# MCU.net
KiCad netlist of a schematic drawn in Altium Designer
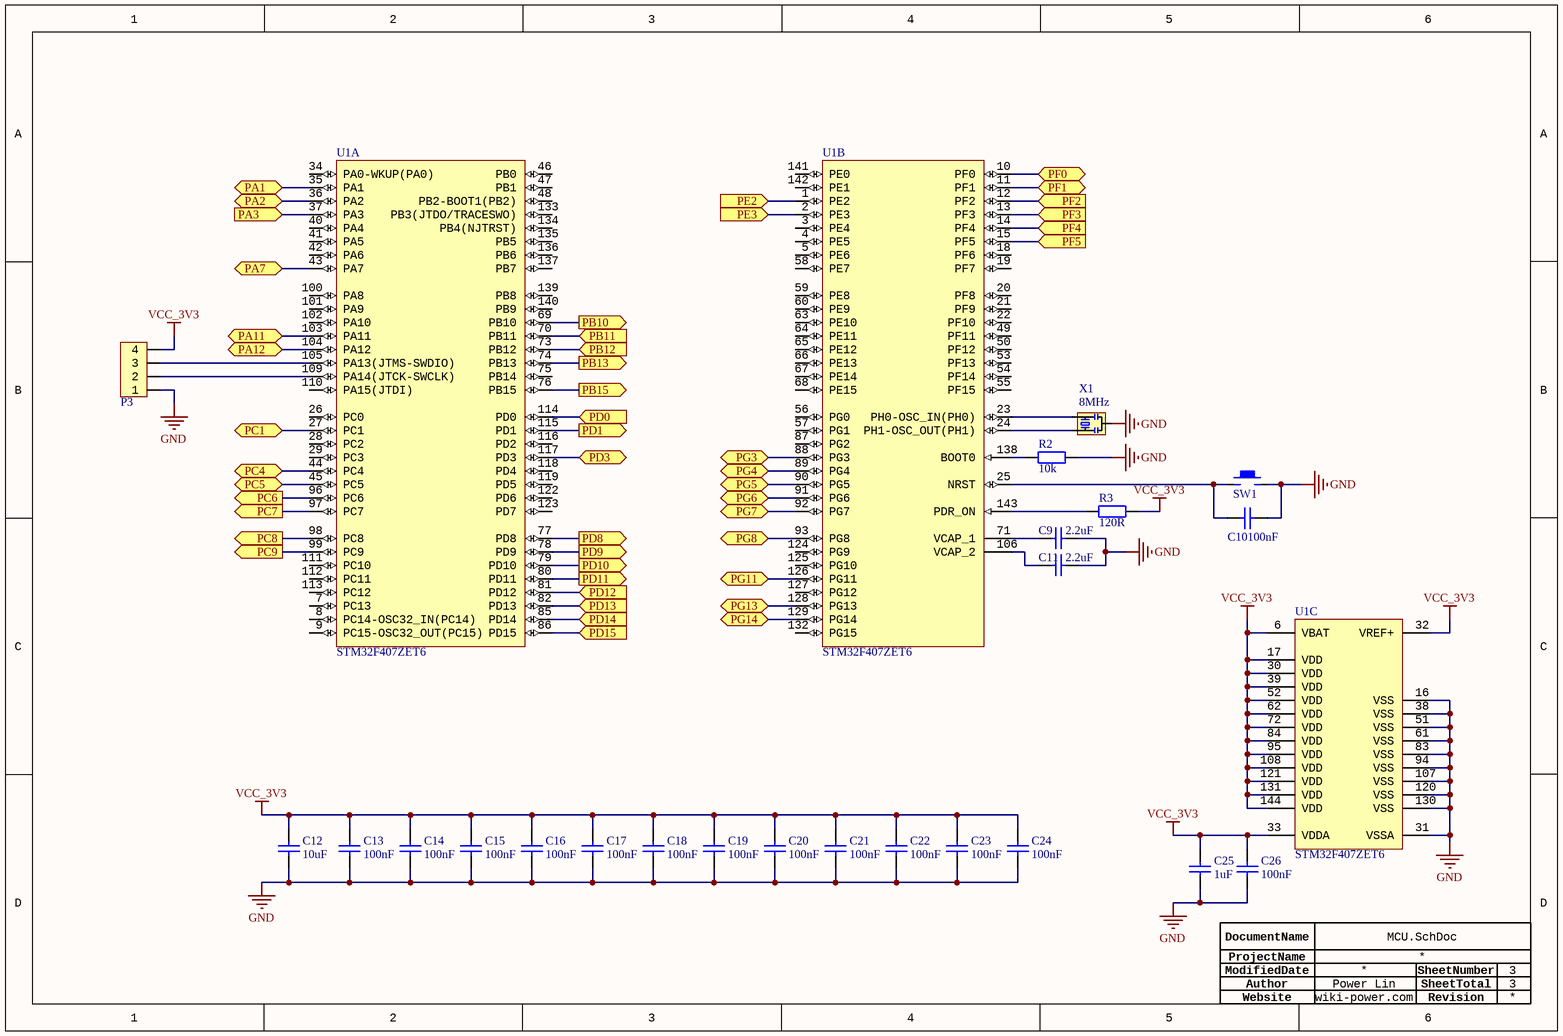
[diagram p0: MCU.SchDoc]

(export (version "E")
  (design (tool "Eeschema 10.0.6"))
  (components
    (comp (ref "C9")
      (value "2.2uF")
      (footprint "CAP-0603")
      (description "贴片电容")
      (libsource (lib "Power_Lib_Altium") (part "CAP"))
    )
    (comp (ref "C10")
      (value "100nF")
      (footprint "CAP-0603")
      (description "贴片电容")
      (libsource (lib "Power_Lib_Altium") (part "CAP"))
    )
    (comp (ref "C11")
      (value "2.2uF")
      (footprint "CAP-0603")
      (description "贴片电容")
      (libsource (lib "Power_Lib_Altium") (part "CAP"))
    )
    (comp (ref "C12")
      (value "10uF")
      (footprint "CAP-0603")
      (description "贴片电容")
      (libsource (lib "Power_Lib_Altium") (part "CAP"))
    )
    (comp (ref "C13")
      (value "100nF")
      (footprint "CAP-0603")
      (description "贴片电容")
      (libsource (lib "Power_Lib_Altium") (part "CAP"))
    )
    (comp (ref "C14")
      (value "100nF")
      (footprint "CAP-0603")
      (description "贴片电容")
      (libsource (lib "Power_Lib_Altium") (part "CAP"))
    )
    (comp (ref "C15")
      (value "100nF")
      (footprint "CAP-0603")
      (description "贴片电容")
      (libsource (lib "Power_Lib_Altium") (part "CAP"))
    )
    (comp (ref "C16")
      (value "100nF")
      (footprint "CAP-0603")
      (description "贴片电容")
      (libsource (lib "Power_Lib_Altium") (part "CAP"))
    )
    (comp (ref "C17")
      (value "100nF")
      (footprint "CAP-0603")
      (description "贴片电容")
      (libsource (lib "Power_Lib_Altium") (part "CAP"))
    )
    (comp (ref "C18")
      (value "100nF")
      (footprint "CAP-0603")
      (description "贴片电容")
      (libsource (lib "Power_Lib_Altium") (part "CAP"))
    )
    (comp (ref "C19")
      (value "100nF")
      (footprint "CAP-0603")
      (description "贴片电容")
      (libsource (lib "Power_Lib_Altium") (part "CAP"))
    )
    (comp (ref "C20")
      (value "100nF")
      (footprint "CAP-0603")
      (description "贴片电容")
      (libsource (lib "Power_Lib_Altium") (part "CAP"))
    )
    (comp (ref "C21")
      (value "100nF")
      (footprint "CAP-0603")
      (description "贴片电容")
      (libsource (lib "Power_Lib_Altium") (part "CAP"))
    )
    (comp (ref "C22")
      (value "100nF")
      (footprint "CAP-0603")
      (description "贴片电容")
      (libsource (lib "Power_Lib_Altium") (part "CAP"))
    )
    (comp (ref "C23")
      (value "100nF")
      (footprint "CAP-0603")
      (description "贴片电容")
      (libsource (lib "Power_Lib_Altium") (part "CAP"))
    )
    (comp (ref "C24")
      (value "100nF")
      (footprint "CAP-0603")
      (description "贴片电容")
      (libsource (lib "Power_Lib_Altium") (part "CAP"))
    )
    (comp (ref "C25")
      (value "1uF")
      (footprint "CAP-0603")
      (description "贴片电容")
      (libsource (lib "Power_Lib_Altium") (part "CAP"))
    )
    (comp (ref "C26")
      (value "100nF")
      (footprint "CAP-0603")
      (description "贴片电容")
      (libsource (lib "Power_Lib_Altium") (part "CAP"))
    )
    (comp (ref "P3")
      (value "HDR1x4_2.54")
      (footprint "HDR1x4_2.54_180")
      (description "Header")
      (libsource (lib "Power_Lib_Altium") (part "HDR1x4_2.54"))
    )
    (comp (ref "R2")
      (value "10k")
      (footprint "R-0603")
      (description "贴片电阻")
      (libsource (lib "Power_Lib_Altium") (part "RES"))
    )
    (comp (ref "R3")
      (value "120R")
      (footprint "R-0603")
      (description "贴片电阻")
      (libsource (lib "Power_Lib_Altium") (part "RES"))
    )
    (comp (ref "SW1")
      (value "KEY")
      (footprint "KEY-4P-4.2*3.4*2.5")
      (description "按键开关")
      (libsource (lib "Power_Lib_Altium") (part "KEY"))
    )
    (comp (ref "U1")
      (value "STM32F407ZET6")
      (footprint "STM-LQFP144_N")
      (fields (field (name "MANUFACTURER") "STMicroelectronics"))
      (libsource (lib "Power_Lib_Altium") (part "STM32F407ZET6"))
    )
    (comp (ref "X1")
      (value "8MHz")
      (footprint "SMD3213-3P")
      (description "CSTCE8M00G15C99-R0")
      (libsource (lib "Power_Lib_Altium") (part "XTAL"))
    )
  )
  (nets
    (net (code "1") (name "/PA1") (class "Default")
      (node (ref "U1") (pin "35") (pinfunction "PA1_35") (pintype "bidirectional"))
    )
    (net (code "2") (name "/PA2") (class "Default")
      (node (ref "U1") (pin "36") (pinfunction "PA2_36") (pintype "bidirectional"))
    )
    (net (code "3") (name "/PA3") (class "Default")
      (node (ref "U1") (pin "37") (pinfunction "PA3_37") (pintype "bidirectional"))
    )
    (net (code "4") (name "/PA7") (class "Default")
      (node (ref "U1") (pin "43") (pinfunction "PA7_43") (pintype "bidirectional"))
    )
    (net (code "5") (name "/PA11") (class "Default")
      (node (ref "U1") (pin "103") (pinfunction "PA11_103") (pintype "bidirectional"))
    )
    (net (code "6") (name "/PA12") (class "Default")
      (node (ref "U1") (pin "104") (pinfunction "PA12_104") (pintype "bidirectional"))
    )
    (net (code "7") (name "/PB10") (class "Default")
      (node (ref "U1") (pin "69") (pinfunction "PB10_69") (pintype "bidirectional"))
    )
    (net (code "8") (name "/PB11") (class "Default")
      (node (ref "U1") (pin "70") (pinfunction "PB11_70") (pintype "bidirectional"))
    )
    (net (code "9") (name "/PB12") (class "Default")
      (node (ref "U1") (pin "73") (pinfunction "PB12_73") (pintype "bidirectional"))
    )
    (net (code "10") (name "/PB13") (class "Default")
      (node (ref "U1") (pin "74") (pinfunction "PB13_74") (pintype "bidirectional"))
    )
    (net (code "11") (name "/PB15") (class "Default")
      (node (ref "U1") (pin "76") (pinfunction "PB15_76") (pintype "bidirectional"))
    )
    (net (code "12") (name "/PC1") (class "Default")
      (node (ref "U1") (pin "27") (pinfunction "PC1_27") (pintype "bidirectional"))
    )
    (net (code "13") (name "/PC4") (class "Default")
      (node (ref "U1") (pin "44") (pinfunction "PC4_44") (pintype "bidirectional"))
    )
    (net (code "14") (name "/PC5") (class "Default")
      (node (ref "U1") (pin "45") (pinfunction "PC5_45") (pintype "bidirectional"))
    )
    (net (code "15") (name "/PC6") (class "Default")
      (node (ref "U1") (pin "96") (pinfunction "PC6_96") (pintype "bidirectional"))
    )
    (net (code "16") (name "/PC7") (class "Default")
      (node (ref "U1") (pin "97") (pinfunction "PC7_97") (pintype "bidirectional"))
    )
    (net (code "17") (name "/PC8") (class "Default")
      (node (ref "U1") (pin "98") (pinfunction "PC8_98") (pintype "bidirectional"))
    )
    (net (code "18") (name "/PC9") (class "Default")
      (node (ref "U1") (pin "99") (pinfunction "PC9_99") (pintype "bidirectional"))
    )
    (net (code "19") (name "/PD0") (class "Default")
      (node (ref "U1") (pin "114") (pinfunction "PD0_114") (pintype "bidirectional"))
    )
    (net (code "20") (name "/PD1") (class "Default")
      (node (ref "U1") (pin "115") (pinfunction "PD1_115") (pintype "bidirectional"))
    )
    (net (code "21") (name "/PD3") (class "Default")
      (node (ref "U1") (pin "117") (pinfunction "PD3_117") (pintype "bidirectional"))
    )
    (net (code "22") (name "/PD8") (class "Default")
      (node (ref "U1") (pin "77") (pinfunction "PD8_77") (pintype "bidirectional"))
    )
    (net (code "23") (name "/PD9") (class "Default")
      (node (ref "U1") (pin "78") (pinfunction "PD9_78") (pintype "bidirectional"))
    )
    (net (code "24") (name "/PD10") (class "Default")
      (node (ref "U1") (pin "79") (pinfunction "PD10_79") (pintype "bidirectional"))
    )
    (net (code "25") (name "/PD11") (class "Default")
      (node (ref "U1") (pin "80") (pinfunction "PD11_80") (pintype "bidirectional"))
    )
    (net (code "26") (name "/PD12") (class "Default")
      (node (ref "U1") (pin "81") (pinfunction "PD12_81") (pintype "bidirectional"))
    )
    (net (code "27") (name "/PD13") (class "Default")
      (node (ref "U1") (pin "82") (pinfunction "PD13_82") (pintype "bidirectional"))
    )
    (net (code "28") (name "/PD14") (class "Default")
      (node (ref "U1") (pin "85") (pinfunction "PD14_85") (pintype "bidirectional"))
    )
    (net (code "29") (name "/PD15") (class "Default")
      (node (ref "U1") (pin "86") (pinfunction "PD15_86") (pintype "bidirectional"))
    )
    (net (code "30") (name "/PE2") (class "Default")
      (node (ref "U1") (pin "1") (pinfunction "PE2_1") (pintype "bidirectional"))
    )
    (net (code "31") (name "/PE3") (class "Default")
      (node (ref "U1") (pin "2") (pinfunction "PE3_2") (pintype "bidirectional"))
    )
    (net (code "32") (name "/PF0") (class "Default")
      (node (ref "U1") (pin "10") (pinfunction "PF0_10") (pintype "bidirectional"))
    )
    (net (code "33") (name "/PF1") (class "Default")
      (node (ref "U1") (pin "11") (pinfunction "PF1_11") (pintype "bidirectional"))
    )
    (net (code "34") (name "/PF2") (class "Default")
      (node (ref "U1") (pin "12") (pinfunction "PF2_12") (pintype "bidirectional"))
    )
    (net (code "35") (name "/PF3") (class "Default")
      (node (ref "U1") (pin "13") (pinfunction "PF3_13") (pintype "bidirectional"))
    )
    (net (code "36") (name "/PF4") (class "Default")
      (node (ref "U1") (pin "14") (pinfunction "PF4_14") (pintype "bidirectional"))
    )
    (net (code "37") (name "/PF5") (class "Default")
      (node (ref "U1") (pin "15") (pinfunction "PF5_15") (pintype "bidirectional"))
    )
    (net (code "38") (name "/PG3") (class "Default")
      (node (ref "U1") (pin "88") (pinfunction "PG3_88") (pintype "bidirectional"))
    )
    (net (code "39") (name "/PG4") (class "Default")
      (node (ref "U1") (pin "89") (pinfunction "PG4_89") (pintype "bidirectional"))
    )
    (net (code "40") (name "/PG5") (class "Default")
      (node (ref "U1") (pin "90") (pinfunction "PG5_90") (pintype "bidirectional"))
    )
    (net (code "41") (name "/PG6") (class "Default")
      (node (ref "U1") (pin "91") (pinfunction "PG6_91") (pintype "bidirectional"))
    )
    (net (code "42") (name "/PG7") (class "Default")
      (node (ref "U1") (pin "92") (pinfunction "PG7_92") (pintype "bidirectional"))
    )
    (net (code "43") (name "/PG8") (class "Default")
      (node (ref "U1") (pin "93") (pinfunction "PG8_93") (pintype "bidirectional"))
    )
    (net (code "44") (name "/PG11") (class "Default")
      (node (ref "U1") (pin "126") (pinfunction "PG11_126") (pintype "bidirectional"))
    )
    (net (code "45") (name "/PG13") (class "Default")
      (node (ref "U1") (pin "128") (pinfunction "PG13_128") (pintype "bidirectional"))
    )
    (net (code "46") (name "/PG14") (class "Default")
      (node (ref "U1") (pin "129") (pinfunction "PG14_129") (pintype "bidirectional"))
    )
    (net (code "47") (name "GND") (class "Default")
      (node (ref "C10") (pin "1") (pinfunction "1_1") (pintype "passive"))
      (node (ref "C11") (pin "2") (pinfunction "2_2") (pintype "passive"))
      (node (ref "C12") (pin "1") (pinfunction "1_1") (pintype "passive"))
      (node (ref "C13") (pin "1") (pinfunction "1_1") (pintype "passive"))
      (node (ref "C14") (pin "1") (pinfunction "1_1") (pintype "passive"))
      (node (ref "C15") (pin "1") (pinfunction "1_1") (pintype "passive"))
      (node (ref "C16") (pin "1") (pinfunction "1_1") (pintype "passive"))
      (node (ref "C17") (pin "1") (pinfunction "1_1") (pintype "passive"))
      (node (ref "C18") (pin "1") (pinfunction "1_1") (pintype "passive"))
      (node (ref "C19") (pin "1") (pinfunction "1_1") (pintype "passive"))
      (node (ref "C20") (pin "1") (pinfunction "1_1") (pintype "passive"))
      (node (ref "C21") (pin "1") (pinfunction "1_1") (pintype "passive"))
      (node (ref "C22") (pin "1") (pinfunction "1_1") (pintype "passive"))
      (node (ref "C23") (pin "1") (pinfunction "1_1") (pintype "passive"))
      (node (ref "C24") (pin "1") (pinfunction "1_1") (pintype "passive"))
      (node (ref "C25") (pin "1") (pinfunction "1_1") (pintype "passive"))
      (node (ref "C26") (pin "1") (pinfunction "1_1") (pintype "passive"))
      (node (ref "C9") (pin "2") (pinfunction "2_2") (pintype "passive"))
      (node (ref "P3") (pin "1") (pinfunction "1_1") (pintype "passive"))
      (node (ref "R2") (pin "1") (pinfunction "1_1") (pintype "passive"))
      (node (ref "SW1") (pin "2") (pinfunction "2_2") (pintype "passive"))
      (node (ref "U1") (pin "107") (pinfunction "VSS_107") (pintype "power_in"))
      (node (ref "U1") (pin "120") (pinfunction "VSS_120") (pintype "power_in"))
      (node (ref "U1") (pin "130") (pinfunction "VSS_130") (pintype "power_in"))
      (node (ref "U1") (pin "16") (pinfunction "VSS_16") (pintype "power_in"))
      (node (ref "U1") (pin "31") (pinfunction "VSSA_31") (pintype "power_in"))
      (node (ref "U1") (pin "38") (pinfunction "VSS_38") (pintype "power_in"))
      (node (ref "U1") (pin "51") (pinfunction "VSS_51") (pintype "power_in"))
      (node (ref "U1") (pin "61") (pinfunction "VSS_61") (pintype "power_in"))
      (node (ref "U1") (pin "83") (pinfunction "VSS_83") (pintype "power_in"))
      (node (ref "U1") (pin "94") (pinfunction "VSS_94") (pintype "power_in"))
      (node (ref "X1") (pin "2") (pinfunction "GND_2") (pintype "passive"))
    )
    (net (code "48") (name "Net-(U1A-PA13(JTMS-SWDIO))") (class "Default")
      (node (ref "P3") (pin "3") (pinfunction "3_3") (pintype "passive"))
      (node (ref "U1") (pin "105") (pinfunction "PA13(JTMS-SWDIO)_105") (pintype "bidirectional"))
    )
    (net (code "49") (name "Net-(U1A-PA14(JTCK-SWCLK))") (class "Default")
      (node (ref "P3") (pin "2") (pinfunction "2_2") (pintype "passive"))
      (node (ref "U1") (pin "109") (pinfunction "PA14(JTCK-SWCLK)_109") (pintype "bidirectional"))
    )
    (net (code "50") (name "Net-(U1B-BOOT0)") (class "Default")
      (node (ref "R2") (pin "2") (pinfunction "2_2") (pintype "passive"))
      (node (ref "U1") (pin "138") (pinfunction "BOOT0_138") (pintype "input"))
    )
    (net (code "51") (name "Net-(U1B-NRST)") (class "Default")
      (node (ref "C10") (pin "2") (pinfunction "2_2") (pintype "passive"))
      (node (ref "SW1") (pin "1") (pinfunction "1_1") (pintype "passive"))
      (node (ref "U1") (pin "25") (pinfunction "NRST_25") (pintype "bidirectional"))
    )
    (net (code "52") (name "Net-(U1B-PDR_ON)") (class "Default")
      (node (ref "R3") (pin "2") (pinfunction "2_2") (pintype "passive"))
      (node (ref "U1") (pin "143") (pinfunction "PDR_ON_143") (pintype "input"))
    )
    (net (code "53") (name "Net-(U1B-PH0-OSC_IN(PH0))") (class "Default")
      (node (ref "U1") (pin "23") (pinfunction "PH0-OSC_IN(PH0)_23") (pintype "bidirectional"))
      (node (ref "X1") (pin "3") (pinfunction "OSC2_3") (pintype "passive"))
    )
    (net (code "54") (name "Net-(U1B-PH1-OSC_OUT(PH1))") (class "Default")
      (node (ref "U1") (pin "24") (pinfunction "PH1-OSC_OUT(PH1)_24") (pintype "bidirectional"))
      (node (ref "X1") (pin "1") (pinfunction "OSC1_1") (pintype "passive"))
    )
    (net (code "55") (name "Net-(U1B-VCAP_1)") (class "Default")
      (node (ref "C9") (pin "1") (pinfunction "1_1") (pintype "passive"))
      (node (ref "U1") (pin "71") (pinfunction "VCAP_1_71") (pintype "power_in"))
    )
    (net (code "56") (name "Net-(U1B-VCAP_2)") (class "Default")
      (node (ref "C11") (pin "1") (pinfunction "1_1") (pintype "passive"))
      (node (ref "U1") (pin "106") (pinfunction "VCAP_2_106") (pintype "power_in"))
    )
    (net (code "57") (name "VCC_3V3") (class "Default")
      (node (ref "C12") (pin "2") (pinfunction "2_2") (pintype "passive"))
      (node (ref "C13") (pin "2") (pinfunction "2_2") (pintype "passive"))
      (node (ref "C14") (pin "2") (pinfunction "2_2") (pintype "passive"))
      (node (ref "C15") (pin "2") (pinfunction "2_2") (pintype "passive"))
      (node (ref "C16") (pin "2") (pinfunction "2_2") (pintype "passive"))
      (node (ref "C17") (pin "2") (pinfunction "2_2") (pintype "passive"))
      (node (ref "C18") (pin "2") (pinfunction "2_2") (pintype "passive"))
      (node (ref "C19") (pin "2") (pinfunction "2_2") (pintype "passive"))
      (node (ref "C20") (pin "2") (pinfunction "2_2") (pintype "passive"))
      (node (ref "C21") (pin "2") (pinfunction "2_2") (pintype "passive"))
      (node (ref "C22") (pin "2") (pinfunction "2_2") (pintype "passive"))
      (node (ref "C23") (pin "2") (pinfunction "2_2") (pintype "passive"))
      (node (ref "C24") (pin "2") (pinfunction "2_2") (pintype "passive"))
      (node (ref "C25") (pin "2") (pinfunction "2_2") (pintype "passive"))
      (node (ref "C26") (pin "2") (pinfunction "2_2") (pintype "passive"))
      (node (ref "P3") (pin "4") (pinfunction "4_4") (pintype "passive"))
      (node (ref "R3") (pin "1") (pinfunction "1_1") (pintype "passive"))
      (node (ref "U1") (pin "108") (pinfunction "VDD_108") (pintype "power_in"))
      (node (ref "U1") (pin "121") (pinfunction "VDD_121") (pintype "power_in"))
      (node (ref "U1") (pin "131") (pinfunction "VDD_131") (pintype "power_in"))
      (node (ref "U1") (pin "144") (pinfunction "VDD_144") (pintype "power_in"))
      (node (ref "U1") (pin "17") (pinfunction "VDD_17") (pintype "power_in"))
      (node (ref "U1") (pin "30") (pinfunction "VDD_30") (pintype "power_in"))
      (node (ref "U1") (pin "32") (pinfunction "VREF+_32") (pintype "power_in"))
      (node (ref "U1") (pin "33") (pinfunction "VDDA_33") (pintype "power_in"))
      (node (ref "U1") (pin "39") (pinfunction "VDD_39") (pintype "power_in"))
      (node (ref "U1") (pin "52") (pinfunction "VDD_52") (pintype "power_in"))
      (node (ref "U1") (pin "6") (pinfunction "VBAT_6") (pintype "power_in"))
      (node (ref "U1") (pin "62") (pinfunction "VDD_62") (pintype "power_in"))
      (node (ref "U1") (pin "72") (pinfunction "VDD_72") (pintype "power_in"))
      (node (ref "U1") (pin "84") (pinfunction "VDD_84") (pintype "power_in"))
      (node (ref "U1") (pin "95") (pinfunction "VDD_95") (pintype "power_in"))
    )
    (net (code "58") (name "unconnected-(U1A-PA0-WKUP(PA0)-Pad34)") (class "Default")
      (node (ref "U1") (pin "34") (pinfunction "PA0-WKUP(PA0)_34") (pintype "bidirectional"))
    )
    (net (code "59") (name "unconnected-(U1A-PA4-Pad40)") (class "Default")
      (node (ref "U1") (pin "40") (pinfunction "PA4_40") (pintype "bidirectional"))
    )
    (net (code "60") (name "unconnected-(U1A-PA5-Pad41)") (class "Default")
      (node (ref "U1") (pin "41") (pinfunction "PA5_41") (pintype "bidirectional"))
    )
    (net (code "61") (name "unconnected-(U1A-PA6-Pad42)") (class "Default")
      (node (ref "U1") (pin "42") (pinfunction "PA6_42") (pintype "bidirectional"))
    )
    (net (code "62") (name "unconnected-(U1A-PA8-Pad100)") (class "Default")
      (node (ref "U1") (pin "100") (pinfunction "PA8_100") (pintype "bidirectional"))
    )
    (net (code "63") (name "unconnected-(U1A-PA9-Pad101)") (class "Default")
      (node (ref "U1") (pin "101") (pinfunction "PA9_101") (pintype "bidirectional"))
    )
    (net (code "64") (name "unconnected-(U1A-PA10-Pad102)") (class "Default")
      (node (ref "U1") (pin "102") (pinfunction "PA10_102") (pintype "bidirectional"))
    )
    (net (code "65") (name "unconnected-(U1A-PA15(JTDI)-Pad110)") (class "Default")
      (node (ref "U1") (pin "110") (pinfunction "PA15(JTDI)_110") (pintype "bidirectional"))
    )
    (net (code "66") (name "unconnected-(U1A-PB0-Pad46)") (class "Default")
      (node (ref "U1") (pin "46") (pinfunction "PB0_46") (pintype "bidirectional"))
    )
    (net (code "67") (name "unconnected-(U1A-PB1-Pad47)") (class "Default")
      (node (ref "U1") (pin "47") (pinfunction "PB1_47") (pintype "bidirectional"))
    )
    (net (code "68") (name "unconnected-(U1A-PB2-BOOT1(PB2)-Pad48)") (class "Default")
      (node (ref "U1") (pin "48") (pinfunction "PB2-BOOT1(PB2)_48") (pintype "bidirectional"))
    )
    (net (code "69") (name "unconnected-(U1A-PB3(JTDO{slash}TRACESWO)-Pad133)") (class "Default")
      (node (ref "U1") (pin "133") (pinfunction "PB3(JTDO/TRACESWO)_133") (pintype "bidirectional"))
    )
    (net (code "70") (name "unconnected-(U1A-PB4(NJTRST)-Pad134)") (class "Default")
      (node (ref "U1") (pin "134") (pinfunction "PB4(NJTRST)_134") (pintype "bidirectional"))
    )
    (net (code "71") (name "unconnected-(U1A-PB5-Pad135)") (class "Default")
      (node (ref "U1") (pin "135") (pinfunction "PB5_135") (pintype "bidirectional"))
    )
    (net (code "72") (name "unconnected-(U1A-PB6-Pad136)") (class "Default")
      (node (ref "U1") (pin "136") (pinfunction "PB6_136") (pintype "bidirectional"))
    )
    (net (code "73") (name "unconnected-(U1A-PB7-Pad137)") (class "Default")
      (node (ref "U1") (pin "137") (pinfunction "PB7_137") (pintype "bidirectional"))
    )
    (net (code "74") (name "unconnected-(U1A-PB8-Pad139)") (class "Default")
      (node (ref "U1") (pin "139") (pinfunction "PB8_139") (pintype "bidirectional"))
    )
    (net (code "75") (name "unconnected-(U1A-PB9-Pad140)") (class "Default")
      (node (ref "U1") (pin "140") (pinfunction "PB9_140") (pintype "bidirectional"))
    )
    (net (code "76") (name "unconnected-(U1A-PB14-Pad75)") (class "Default")
      (node (ref "U1") (pin "75") (pinfunction "PB14_75") (pintype "bidirectional"))
    )
    (net (code "77") (name "unconnected-(U1A-PC0-Pad26)") (class "Default")
      (node (ref "U1") (pin "26") (pinfunction "PC0_26") (pintype "bidirectional"))
    )
    (net (code "78") (name "unconnected-(U1A-PC2-Pad28)") (class "Default")
      (node (ref "U1") (pin "28") (pinfunction "PC2_28") (pintype "bidirectional"))
    )
    (net (code "79") (name "unconnected-(U1A-PC3-Pad29)") (class "Default")
      (node (ref "U1") (pin "29") (pinfunction "PC3_29") (pintype "bidirectional"))
    )
    (net (code "80") (name "unconnected-(U1A-PC10-Pad111)") (class "Default")
      (node (ref "U1") (pin "111") (pinfunction "PC10_111") (pintype "bidirectional"))
    )
    (net (code "81") (name "unconnected-(U1A-PC11-Pad112)") (class "Default")
      (node (ref "U1") (pin "112") (pinfunction "PC11_112") (pintype "bidirectional"))
    )
    (net (code "82") (name "unconnected-(U1A-PC12-Pad113)") (class "Default")
      (node (ref "U1") (pin "113") (pinfunction "PC12_113") (pintype "bidirectional"))
    )
    (net (code "83") (name "unconnected-(U1A-PC13-Pad7)") (class "Default")
      (node (ref "U1") (pin "7") (pinfunction "PC13_7") (pintype "bidirectional"))
    )
    (net (code "84") (name "unconnected-(U1A-PC14-OSC32_IN(PC14)-Pad8)") (class "Default")
      (node (ref "U1") (pin "8") (pinfunction "PC14-OSC32_IN(PC14)_8") (pintype "bidirectional"))
    )
    (net (code "85") (name "unconnected-(U1A-PC15-OSC32_OUT(PC15)-Pad9)") (class "Default")
      (node (ref "U1") (pin "9") (pinfunction "PC15-OSC32_OUT(PC15)_9") (pintype "bidirectional"))
    )
    (net (code "86") (name "unconnected-(U1A-PD2-Pad116)") (class "Default")
      (node (ref "U1") (pin "116") (pinfunction "PD2_116") (pintype "bidirectional"))
    )
    (net (code "87") (name "unconnected-(U1A-PD4-Pad118)") (class "Default")
      (node (ref "U1") (pin "118") (pinfunction "PD4_118") (pintype "bidirectional"))
    )
    (net (code "88") (name "unconnected-(U1A-PD5-Pad119)") (class "Default")
      (node (ref "U1") (pin "119") (pinfunction "PD5_119") (pintype "bidirectional"))
    )
    (net (code "89") (name "unconnected-(U1A-PD6-Pad122)") (class "Default")
      (node (ref "U1") (pin "122") (pinfunction "PD6_122") (pintype "bidirectional"))
    )
    (net (code "90") (name "unconnected-(U1A-PD7-Pad123)") (class "Default")
      (node (ref "U1") (pin "123") (pinfunction "PD7_123") (pintype "bidirectional"))
    )
    (net (code "91") (name "unconnected-(U1B-PE0-Pad141)") (class "Default")
      (node (ref "U1") (pin "141") (pinfunction "PE0_141") (pintype "bidirectional"))
    )
    (net (code "92") (name "unconnected-(U1B-PE1-Pad142)") (class "Default")
      (node (ref "U1") (pin "142") (pinfunction "PE1_142") (pintype "bidirectional"))
    )
    (net (code "93") (name "unconnected-(U1B-PE4-Pad3)") (class "Default")
      (node (ref "U1") (pin "3") (pinfunction "PE4_3") (pintype "bidirectional"))
    )
    (net (code "94") (name "unconnected-(U1B-PE5-Pad4)") (class "Default")
      (node (ref "U1") (pin "4") (pinfunction "PE5_4") (pintype "bidirectional"))
    )
    (net (code "95") (name "unconnected-(U1B-PE6-Pad5)") (class "Default")
      (node (ref "U1") (pin "5") (pinfunction "PE6_5") (pintype "bidirectional"))
    )
    (net (code "96") (name "unconnected-(U1B-PE7-Pad58)") (class "Default")
      (node (ref "U1") (pin "58") (pinfunction "PE7_58") (pintype "bidirectional"))
    )
    (net (code "97") (name "unconnected-(U1B-PE8-Pad59)") (class "Default")
      (node (ref "U1") (pin "59") (pinfunction "PE8_59") (pintype "bidirectional"))
    )
    (net (code "98") (name "unconnected-(U1B-PE9-Pad60)") (class "Default")
      (node (ref "U1") (pin "60") (pinfunction "PE9_60") (pintype "bidirectional"))
    )
    (net (code "99") (name "unconnected-(U1B-PE10-Pad63)") (class "Default")
      (node (ref "U1") (pin "63") (pinfunction "PE10_63") (pintype "bidirectional"))
    )
    (net (code "100") (name "unconnected-(U1B-PE11-Pad64)") (class "Default")
      (node (ref "U1") (pin "64") (pinfunction "PE11_64") (pintype "bidirectional"))
    )
    (net (code "101") (name "unconnected-(U1B-PE12-Pad65)") (class "Default")
      (node (ref "U1") (pin "65") (pinfunction "PE12_65") (pintype "bidirectional"))
    )
    (net (code "102") (name "unconnected-(U1B-PE13-Pad66)") (class "Default")
      (node (ref "U1") (pin "66") (pinfunction "PE13_66") (pintype "bidirectional"))
    )
    (net (code "103") (name "unconnected-(U1B-PE14-Pad67)") (class "Default")
      (node (ref "U1") (pin "67") (pinfunction "PE14_67") (pintype "bidirectional"))
    )
    (net (code "104") (name "unconnected-(U1B-PE15-Pad68)") (class "Default")
      (node (ref "U1") (pin "68") (pinfunction "PE15_68") (pintype "bidirectional"))
    )
    (net (code "105") (name "unconnected-(U1B-PF6-Pad18)") (class "Default")
      (node (ref "U1") (pin "18") (pinfunction "PF6_18") (pintype "bidirectional"))
    )
    (net (code "106") (name "unconnected-(U1B-PF7-Pad19)") (class "Default")
      (node (ref "U1") (pin "19") (pinfunction "PF7_19") (pintype "bidirectional"))
    )
    (net (code "107") (name "unconnected-(U1B-PF8-Pad20)") (class "Default")
      (node (ref "U1") (pin "20") (pinfunction "PF8_20") (pintype "bidirectional"))
    )
    (net (code "108") (name "unconnected-(U1B-PF9-Pad21)") (class "Default")
      (node (ref "U1") (pin "21") (pinfunction "PF9_21") (pintype "bidirectional"))
    )
    (net (code "109") (name "unconnected-(U1B-PF10-Pad22)") (class "Default")
      (node (ref "U1") (pin "22") (pinfunction "PF10_22") (pintype "bidirectional"))
    )
    (net (code "110") (name "unconnected-(U1B-PF11-Pad49)") (class "Default")
      (node (ref "U1") (pin "49") (pinfunction "PF11_49") (pintype "bidirectional"))
    )
    (net (code "111") (name "unconnected-(U1B-PF12-Pad50)") (class "Default")
      (node (ref "U1") (pin "50") (pinfunction "PF12_50") (pintype "bidirectional"))
    )
    (net (code "112") (name "unconnected-(U1B-PF13-Pad53)") (class "Default")
      (node (ref "U1") (pin "53") (pinfunction "PF13_53") (pintype "bidirectional"))
    )
    (net (code "113") (name "unconnected-(U1B-PF14-Pad54)") (class "Default")
      (node (ref "U1") (pin "54") (pinfunction "PF14_54") (pintype "bidirectional"))
    )
    (net (code "114") (name "unconnected-(U1B-PF15-Pad55)") (class "Default")
      (node (ref "U1") (pin "55") (pinfunction "PF15_55") (pintype "bidirectional"))
    )
    (net (code "115") (name "unconnected-(U1B-PG0-Pad56)") (class "Default")
      (node (ref "U1") (pin "56") (pinfunction "PG0_56") (pintype "bidirectional"))
    )
    (net (code "116") (name "unconnected-(U1B-PG1-Pad57)") (class "Default")
      (node (ref "U1") (pin "57") (pinfunction "PG1_57") (pintype "bidirectional"))
    )
    (net (code "117") (name "unconnected-(U1B-PG2-Pad87)") (class "Default")
      (node (ref "U1") (pin "87") (pinfunction "PG2_87") (pintype "bidirectional"))
    )
    (net (code "118") (name "unconnected-(U1B-PG9-Pad124)") (class "Default")
      (node (ref "U1") (pin "124") (pinfunction "PG9_124") (pintype "bidirectional"))
    )
    (net (code "119") (name "unconnected-(U1B-PG10-Pad125)") (class "Default")
      (node (ref "U1") (pin "125") (pinfunction "PG10_125") (pintype "bidirectional"))
    )
    (net (code "120") (name "unconnected-(U1B-PG12-Pad127)") (class "Default")
      (node (ref "U1") (pin "127") (pinfunction "PG12_127") (pintype "bidirectional"))
    )
    (net (code "121") (name "unconnected-(U1B-PG15-Pad132)") (class "Default")
      (node (ref "U1") (pin "132") (pinfunction "PG15_132") (pintype "bidirectional"))
    )
  )
)
